# vesc_drv8301.net
KiCad netlist of a schematic drawn in Altium Designer
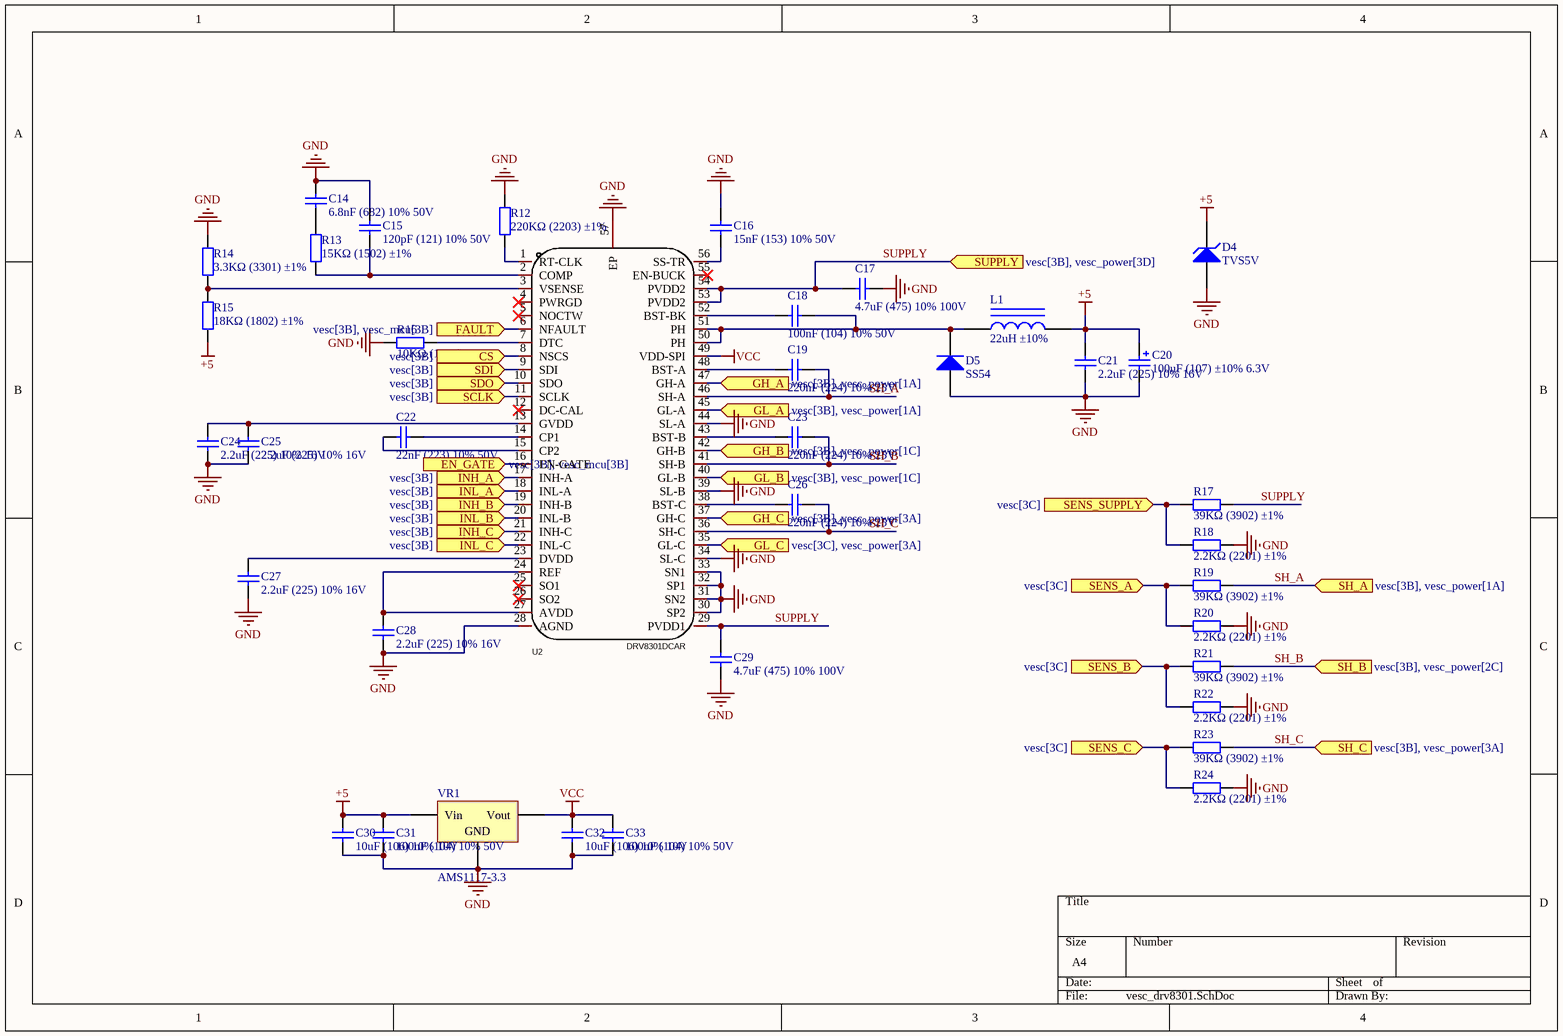
[diagram p0: vesc_drv8301.SchDoc]

(export (version "E")
  (design (tool "Eeschema 10.0.6"))
  (components
    (comp (ref "C14")
      (value "6.8nF (682) 10% 50V")
      (footprint "0603_C")
      (description "贴片电容")
      (libsource (lib "Miscellaneous Devices LC") (part "0603 6.8nF (682) 10% 50V"))
    )
    (comp (ref "C15")
      (value "120pF (121) 10% 50V")
      (footprint "0603_C")
      (description "贴片电容")
      (libsource (lib "Miscellaneous Devices LC") (part "0603 150pF (151) 10% 50V"))
    )
    (comp (ref "C16")
      (value "15nF (153) 10% 50V")
      (footprint "0603_C")
      (description "贴片电容")
      (libsource (lib "Miscellaneous Devices LC") (part "0603 15nF (153) 10% 50V"))
    )
    (comp (ref "C17")
      (value "4.7uF (475) 10% 100V")
      (footprint "1210_C")
      (description "贴片电容")
      (libsource (lib "Miscellaneous Devices LC") (part "1206 4.7uF (475) 10% 50V"))
    )
    (comp (ref "C18")
      (value "100nF (104) 10% 50V")
      (footprint "0603_C")
      (description "贴片电容")
      (libsource (lib "Miscellaneous Devices LC") (part "0603 100nF (104) 10% 50V"))
    )
    (comp (ref "C19")
      (value "220nF (224) 10% 25V")
      (footprint "0603_C")
      (description "贴片电容")
      (libsource (lib "Miscellaneous Devices LC") (part "0603 220nF (224) 10% 25V"))
    )
    (comp (ref "C20")
      (value "100uF (107) ±10% 6.3V")
      (footprint "CASE-B_3528")
      (description "钽电容")
      (libsource (lib "Miscellaneous Devices LC") (part "3528 100uF (107) 10% 6.3V"))
    )
    (comp (ref "C21")
      (value "2.2uF (225) 10% 16V")
      (footprint "0603_C")
      (description "贴片电容")
      (libsource (lib "Miscellaneous Devices LC") (part "0603 2.2uF (225) 10% 16V"))
    )
    (comp (ref "C22")
      (value "22nF (223) 10% 50V")
      (footprint "0603_C")
      (description "贴片电容")
      (libsource (lib "Miscellaneous Devices LC") (part "0603 22nF (223) 10% 50V"))
    )
    (comp (ref "C23")
      (value "220nF (224) 10% 25V")
      (footprint "0603_C")
      (description "贴片电容")
      (libsource (lib "Miscellaneous Devices LC") (part "0603 220nF (224) 10% 25V"))
    )
    (comp (ref "C24")
      (value "2.2uF (225) 10% 16V")
      (footprint "0603_C")
      (description "贴片电容")
      (libsource (lib "Miscellaneous Devices LC") (part "0603 2.2uF (225) 10% 16V"))
    )
    (comp (ref "C25")
      (value "2.2uF (225) 10% 16V")
      (footprint "0603_C")
      (description "贴片电容")
      (libsource (lib "Miscellaneous Devices LC") (part "0603 2.2uF (225) 10% 16V"))
    )
    (comp (ref "C26")
      (value "220nF (224) 10% 25V")
      (footprint "0603_C")
      (description "贴片电容")
      (libsource (lib "Miscellaneous Devices LC") (part "0603 220nF (224) 10% 25V"))
    )
    (comp (ref "C27")
      (value "2.2uF (225) 10% 16V")
      (footprint "0603_C")
      (description "贴片电容")
      (libsource (lib "Miscellaneous Devices LC") (part "0603 2.2uF (225) 10% 16V"))
    )
    (comp (ref "C28")
      (value "2.2uF (225) 10% 16V")
      (footprint "0603_C")
      (description "贴片电容")
      (libsource (lib "Miscellaneous Devices LC") (part "0603 2.2uF (225) 10% 16V"))
    )
    (comp (ref "C29")
      (value "4.7uF (475) 10% 100V")
      (footprint "1210_C")
      (description "贴片电容")
      (libsource (lib "Miscellaneous Devices LC") (part "1206 4.7uF (475) 10% 50V"))
    )
    (comp (ref "C30")
      (value "10uF (106) 10% 10V")
      (footprint "0603_C")
      (description "贴片电容")
      (libsource (lib "Miscellaneous Devices LC") (part "0603 10uF (106) 10% 10V"))
    )
    (comp (ref "C31")
      (value "100nF (104) 10% 50V")
      (footprint "0603_C")
      (description "贴片电容")
      (libsource (lib "Miscellaneous Devices LC") (part "0603 100nF (104) 10% 50V"))
    )
    (comp (ref "C32")
      (value "10uF (106) 10% 10V")
      (footprint "0603_C")
      (description "贴片电容")
      (libsource (lib "Miscellaneous Devices LC") (part "0603 10uF (106) 10% 10V"))
    )
    (comp (ref "C33")
      (value "100nF (104) 10% 50V")
      (footprint "0603_C")
      (description "贴片电容")
      (libsource (lib "Miscellaneous Devices LC") (part "0603 100nF (104) 10% 50V"))
    )
    (comp (ref "D4")
      (value "TVS5V")
      (footprint "SMA(DO-214AC)_S2")
      (description "稳压二极管")
      (libsource (lib "Miscellaneous Devices LC") (part "LL-34 ZMM5V6"))
    )
    (comp (ref "D5")
      (value "SS54")
      (footprint "SMA(DO-214AC)_S1")
      (description "二极管")
      (libsource (lib "Miscellaneous Devices LC") (part "SMA(DO-214AC) SS54"))
    )
    (comp (ref "L1")
      (value "22uH ±10%")
      (footprint "IND-SMD_L7.3-W6.6")
      (description "贴片电感")
      (libsource (lib "Miscellaneous Devices LC") (part "0805 22uH 10%"))
    )
    (comp (ref "R12")
      (value "220KΩ (2203) ±1%")
      (footprint "0603_R")
      (description "贴片电阻")
      (libsource (lib "Miscellaneous Devices LC") (part "0603 220KΩ (2203) 1%"))
    )
    (comp (ref "R13")
      (value "15KΩ (1502) ±1%")
      (footprint "0603_R")
      (description "贴片电阻")
      (libsource (lib "Miscellaneous Devices LC") (part "0603 15KΩ (1502) 1%"))
    )
    (comp (ref "R14")
      (value "3.3KΩ (3301) ±1%")
      (footprint "0603_R")
      (description "贴片电阻")
      (libsource (lib "Miscellaneous Devices LC") (part "0603 3.3KΩ (3301) 1%"))
    )
    (comp (ref "R15")
      (value "18KΩ (1802) ±1%")
      (footprint "0603_R")
      (description "贴片电阻")
      (libsource (lib "Miscellaneous Devices LC") (part "0603 18KΩ (1802) 1%"))
    )
    (comp (ref "R16")
      (value "10KΩ (1002) ±1%")
      (footprint "0603_R")
      (description "贴片电阻")
      (libsource (lib "Miscellaneous Devices LC") (part "0603 10KΩ (1002) 1%"))
    )
    (comp (ref "R17")
      (value "39KΩ (3902) ±1%")
      (footprint "0603_R")
      (description "贴片电阻")
      (libsource (lib "Miscellaneous Devices LC") (part "0603 39KΩ (3902) 1%"))
    )
    (comp (ref "R18")
      (value "2.2KΩ (2201) ±1%")
      (footprint "0603_R")
      (description "贴片电阻")
      (libsource (lib "Miscellaneous Devices LC") (part "0603 2.2KΩ (2201) 1%"))
    )
    (comp (ref "R19")
      (value "39KΩ (3902) ±1%")
      (footprint "0603_R")
      (description "贴片电阻")
      (libsource (lib "Miscellaneous Devices LC") (part "0603 39KΩ (3902) 1%"))
    )
    (comp (ref "R20")
      (value "2.2KΩ (2201) ±1%")
      (footprint "0603_R")
      (description "贴片电阻")
      (libsource (lib "Miscellaneous Devices LC") (part "0603 2.2KΩ (2201) 1%"))
    )
    (comp (ref "R21")
      (value "39KΩ (3902) ±1%")
      (footprint "0603_R")
      (description "贴片电阻")
      (libsource (lib "Miscellaneous Devices LC") (part "0603 39KΩ (3902) 1%"))
    )
    (comp (ref "R22")
      (value "2.2KΩ (2201) ±1%")
      (footprint "0603_R")
      (description "贴片电阻")
      (libsource (lib "Miscellaneous Devices LC") (part "0603 2.2KΩ (2201) 1%"))
    )
    (comp (ref "R23")
      (value "39KΩ (3902) ±1%")
      (footprint "0603_R")
      (description "贴片电阻")
      (libsource (lib "Miscellaneous Devices LC") (part "0603 39KΩ (3902) 1%"))
    )
    (comp (ref "R24")
      (value "2.2KΩ (2201) ±1%")
      (footprint "0603_R")
      (description "贴片电阻")
      (libsource (lib "Miscellaneous Devices LC") (part "0603 2.2KΩ (2201) 1%"))
    )
    (comp (ref "U2")
      (value "DRV8301DCAR")
      (footprint "HTSSOP-56_L14.0-W6.0-P0.50-LS8.0-BL")
      (fields (field (name "MANUFACTURER") "TI(德州仪器)"))
      (libsource (lib "vesc") (part "DRV8301DCAR"))
    )
    (comp (ref "VR1")
      (value "AMS1117-3.3")
      (footprint "SOT-223")
      (description "低压差线性稳压(LDO)")
      (libsource (lib "Miscellaneous Devices LC") (part "SOT-223 AMS1117-3.3"))
    )
  )
  (nets
    (net (code "1") (name "+5") (class "Default")
      (node (ref "C20") (pin "1") (pinfunction "1_1") (pintype "passive"))
      (node (ref "C21") (pin "2") (pinfunction "2_2") (pintype "passive"))
      (node (ref "C30") (pin "2") (pinfunction "2_2") (pintype "passive"))
      (node (ref "C31") (pin "2") (pinfunction "2_2") (pintype "passive"))
      (node (ref "D4") (pin "2") (pinfunction "K_2") (pintype "passive"))
      (node (ref "L1") (pin "2") (pinfunction "2_2") (pintype "passive"))
      (node (ref "R15") (pin "1") (pinfunction "1_1") (pintype "passive"))
      (node (ref "VR1") (pin "3") (pinfunction "Vin_3") (pintype "passive"))
    )
    (net (code "2") (name "/CS") (class "Default")
      (node (ref "U2") (pin "8") (pinfunction "NSCS_8") (pintype "passive"))
    )
    (net (code "3") (name "/EN_GATE") (class "Default")
      (node (ref "U2") (pin "16") (pinfunction "EN-GATE_16") (pintype "passive"))
    )
    (net (code "4") (name "/FAULT") (class "Default")
      (node (ref "U2") (pin "6") (pinfunction "NFAULT_6") (pintype "passive"))
    )
    (net (code "5") (name "/GH_A") (class "Default")
      (node (ref "U2") (pin "47") (pinfunction "GH-A_47") (pintype "passive"))
    )
    (net (code "6") (name "/GH_B") (class "Default")
      (node (ref "U2") (pin "42") (pinfunction "GH-B_42") (pintype "passive"))
    )
    (net (code "7") (name "/GH_C") (class "Default")
      (node (ref "U2") (pin "37") (pinfunction "GH-C_37") (pintype "passive"))
    )
    (net (code "8") (name "/GL_A") (class "Default")
      (node (ref "U2") (pin "45") (pinfunction "GL-A_45") (pintype "passive"))
    )
    (net (code "9") (name "/GL_B") (class "Default")
      (node (ref "U2") (pin "40") (pinfunction "GL-B_40") (pintype "passive"))
    )
    (net (code "10") (name "/GL_C") (class "Default")
      (node (ref "U2") (pin "35") (pinfunction "GL-C_35") (pintype "passive"))
    )
    (net (code "11") (name "/INH_A") (class "Default")
      (node (ref "U2") (pin "17") (pinfunction "INH-A_17") (pintype "passive"))
    )
    (net (code "12") (name "/INH_B") (class "Default")
      (node (ref "U2") (pin "19") (pinfunction "INH-B_19") (pintype "passive"))
    )
    (net (code "13") (name "/INH_C") (class "Default")
      (node (ref "U2") (pin "21") (pinfunction "INH-C_21") (pintype "passive"))
    )
    (net (code "14") (name "/INL_A") (class "Default")
      (node (ref "U2") (pin "18") (pinfunction "INL-A_18") (pintype "passive"))
    )
    (net (code "15") (name "/INL_B") (class "Default")
      (node (ref "U2") (pin "20") (pinfunction "INL-B_20") (pintype "passive"))
    )
    (net (code "16") (name "/INL_C") (class "Default")
      (node (ref "U2") (pin "22") (pinfunction "INL-C_22") (pintype "passive"))
    )
    (net (code "17") (name "/SCLK") (class "Default")
      (node (ref "U2") (pin "11") (pinfunction "SCLK_11") (pintype "passive"))
    )
    (net (code "18") (name "/SDI") (class "Default")
      (node (ref "U2") (pin "9") (pinfunction "SDI_9") (pintype "passive"))
    )
    (net (code "19") (name "/SDO") (class "Default")
      (node (ref "U2") (pin "10") (pinfunction "SDO_10") (pintype "passive"))
    )
    (net (code "20") (name "/SENS_A") (class "Default")
      (node (ref "R19") (pin "1") (pinfunction "1_1") (pintype "passive"))
      (node (ref "R20") (pin "1") (pinfunction "1_1") (pintype "passive"))
    )
    (net (code "21") (name "/SENS_B") (class "Default")
      (node (ref "R21") (pin "1") (pinfunction "1_1") (pintype "passive"))
      (node (ref "R22") (pin "1") (pinfunction "1_1") (pintype "passive"))
    )
    (net (code "22") (name "/SENS_C") (class "Default")
      (node (ref "R23") (pin "1") (pinfunction "1_1") (pintype "passive"))
      (node (ref "R24") (pin "1") (pinfunction "1_1") (pintype "passive"))
    )
    (net (code "23") (name "/SENS_SUPPLY") (class "Default")
      (node (ref "R17") (pin "1") (pinfunction "1_1") (pintype "passive"))
      (node (ref "R18") (pin "1") (pinfunction "1_1") (pintype "passive"))
    )
    (net (code "24") (name "/SH_A") (class "Default")
      (node (ref "C19") (pin "2") (pinfunction "2_2") (pintype "passive"))
      (node (ref "R19") (pin "2") (pinfunction "2_2") (pintype "passive"))
      (node (ref "U2") (pin "46") (pinfunction "SH-A_46") (pintype "passive"))
    )
    (net (code "25") (name "/SH_B") (class "Default")
      (node (ref "C23") (pin "2") (pinfunction "2_2") (pintype "passive"))
      (node (ref "R21") (pin "2") (pinfunction "2_2") (pintype "passive"))
      (node (ref "U2") (pin "41") (pinfunction "SH-B_41") (pintype "passive"))
    )
    (net (code "26") (name "/SH_C") (class "Default")
      (node (ref "C26") (pin "2") (pinfunction "2_2") (pintype "passive"))
      (node (ref "R23") (pin "2") (pinfunction "2_2") (pintype "passive"))
      (node (ref "U2") (pin "36") (pinfunction "SH-C_36") (pintype "passive"))
    )
    (net (code "27") (name "/SUPPLY") (class "Default")
      (node (ref "C17") (pin "1") (pinfunction "1_1") (pintype "passive"))
      (node (ref "C29") (pin "2") (pinfunction "2_2") (pintype "passive"))
      (node (ref "R17") (pin "2") (pinfunction "2_2") (pintype "passive"))
      (node (ref "U2") (pin "29") (pinfunction "PVDD1_29") (pintype "passive"))
      (node (ref "U2") (pin "53") (pinfunction "PVDD2_53") (pintype "passive"))
      (node (ref "U2") (pin "54") (pinfunction "PVDD2_54") (pintype "passive"))
    )
    (net (code "28") (name "GND") (class "Default")
      (node (ref "C14") (pin "2") (pinfunction "2_2") (pintype "passive"))
      (node (ref "C15") (pin "2") (pinfunction "2_2") (pintype "passive"))
      (node (ref "C16") (pin "2") (pinfunction "2_2") (pintype "passive"))
      (node (ref "C17") (pin "2") (pinfunction "2_2") (pintype "passive"))
      (node (ref "C20") (pin "2") (pinfunction "2_2") (pintype "passive"))
      (node (ref "C21") (pin "1") (pinfunction "1_1") (pintype "passive"))
      (node (ref "C24") (pin "1") (pinfunction "1_1") (pintype "passive"))
      (node (ref "C25") (pin "1") (pinfunction "1_1") (pintype "passive"))
      (node (ref "C27") (pin "1") (pinfunction "1_1") (pintype "passive"))
      (node (ref "C28") (pin "1") (pinfunction "1_1") (pintype "passive"))
      (node (ref "C29") (pin "1") (pinfunction "1_1") (pintype "passive"))
      (node (ref "C30") (pin "1") (pinfunction "1_1") (pintype "passive"))
      (node (ref "C31") (pin "1") (pinfunction "1_1") (pintype "passive"))
      (node (ref "C32") (pin "1") (pinfunction "1_1") (pintype "passive"))
      (node (ref "C33") (pin "1") (pinfunction "1_1") (pintype "passive"))
      (node (ref "D4") (pin "1") (pinfunction "A_1") (pintype "passive"))
      (node (ref "D5") (pin "1") (pinfunction "A_1") (pintype "passive"))
      (node (ref "R12") (pin "2") (pinfunction "2_2") (pintype "passive"))
      (node (ref "R14") (pin "2") (pinfunction "2_2") (pintype "passive"))
      (node (ref "R16") (pin "1") (pinfunction "1_1") (pintype "passive"))
      (node (ref "R18") (pin "2") (pinfunction "2_2") (pintype "passive"))
      (node (ref "R20") (pin "2") (pinfunction "2_2") (pintype "passive"))
      (node (ref "R22") (pin "2") (pinfunction "2_2") (pintype "passive"))
      (node (ref "R24") (pin "2") (pinfunction "2_2") (pintype "passive"))
      (node (ref "U2") (pin "28") (pinfunction "AGND_28") (pintype "passive"))
      (node (ref "U2") (pin "30") (pinfunction "SP2_30") (pintype "passive"))
      (node (ref "U2") (pin "31") (pinfunction "SN2_31") (pintype "passive"))
      (node (ref "U2") (pin "32") (pinfunction "SP1_32") (pintype "passive"))
      (node (ref "U2") (pin "33") (pinfunction "SN1_33") (pintype "passive"))
      (node (ref "U2") (pin "34") (pinfunction "SL-C_34") (pintype "passive"))
      (node (ref "U2") (pin "39") (pinfunction "SL-B_39") (pintype "passive"))
      (node (ref "U2") (pin "44") (pinfunction "SL-A_44") (pintype "passive"))
      (node (ref "U2") (pin "57") (pinfunction "EP_57") (pintype "passive"))
      (node (ref "VR1") (pin "1") (pinfunction "GND_1") (pintype "passive"))
    )
    (net (code "29") (name "Net-(C14-Pad1)") (class "Default")
      (node (ref "C14") (pin "1") (pinfunction "1_1") (pintype "passive"))
      (node (ref "R13") (pin "2") (pinfunction "2_2") (pintype "passive"))
    )
    (net (code "30") (name "Net-(D5-K)") (class "Default")
      (node (ref "C18") (pin "2") (pinfunction "2_2") (pintype "passive"))
      (node (ref "D5") (pin "2") (pinfunction "K_2") (pintype "passive"))
      (node (ref "L1") (pin "1") (pinfunction "1_1") (pintype "passive"))
      (node (ref "U2") (pin "50") (pinfunction "PH_50") (pintype "passive"))
      (node (ref "U2") (pin "51") (pinfunction "PH_51") (pintype "passive"))
    )
    (net (code "31") (name "Net-(U2-AVDD)") (class "Default")
      (node (ref "C28") (pin "2") (pinfunction "2_2") (pintype "passive"))
      (node (ref "U2") (pin "24") (pinfunction "REF_24") (pintype "passive"))
      (node (ref "U2") (pin "27") (pinfunction "AVDD_27") (pintype "passive"))
    )
    (net (code "32") (name "Net-(U2-BST-A)") (class "Default")
      (node (ref "C19") (pin "1") (pinfunction "1_1") (pintype "passive"))
      (node (ref "U2") (pin "48") (pinfunction "BST-A_48") (pintype "passive"))
    )
    (net (code "33") (name "Net-(U2-BST-B)") (class "Default")
      (node (ref "C23") (pin "1") (pinfunction "1_1") (pintype "passive"))
      (node (ref "U2") (pin "43") (pinfunction "BST-B_43") (pintype "passive"))
    )
    (net (code "34") (name "Net-(U2-BST-BK)") (class "Default")
      (node (ref "C18") (pin "1") (pinfunction "1_1") (pintype "passive"))
      (node (ref "U2") (pin "52") (pinfunction "BST-BK_52") (pintype "passive"))
    )
    (net (code "35") (name "Net-(U2-BST-C)") (class "Default")
      (node (ref "C26") (pin "1") (pinfunction "1_1") (pintype "passive"))
      (node (ref "U2") (pin "38") (pinfunction "BST-C_38") (pintype "passive"))
    )
    (net (code "36") (name "Net-(U2-COMP)") (class "Default")
      (node (ref "C15") (pin "1") (pinfunction "1_1") (pintype "passive"))
      (node (ref "R13") (pin "1") (pinfunction "1_1") (pintype "passive"))
      (node (ref "U2") (pin "2") (pinfunction "COMP_2") (pintype "passive"))
    )
    (net (code "37") (name "Net-(U2-CP1)") (class "Default")
      (node (ref "C22") (pin "2") (pinfunction "2_2") (pintype "passive"))
      (node (ref "U2") (pin "14") (pinfunction "CP1_14") (pintype "passive"))
    )
    (net (code "38") (name "Net-(U2-CP2)") (class "Default")
      (node (ref "C22") (pin "1") (pinfunction "1_1") (pintype "passive"))
      (node (ref "U2") (pin "15") (pinfunction "CP2_15") (pintype "passive"))
    )
    (net (code "39") (name "Net-(U2-DTC)") (class "Default")
      (node (ref "R16") (pin "2") (pinfunction "2_2") (pintype "passive"))
      (node (ref "U2") (pin "7") (pinfunction "DTC_7") (pintype "passive"))
    )
    (net (code "40") (name "Net-(U2-DVDD)") (class "Default")
      (node (ref "C27") (pin "2") (pinfunction "2_2") (pintype "passive"))
      (node (ref "U2") (pin "23") (pinfunction "DVDD_23") (pintype "passive"))
    )
    (net (code "41") (name "Net-(U2-GVDD)") (class "Default")
      (node (ref "C24") (pin "2") (pinfunction "2_2") (pintype "passive"))
      (node (ref "C25") (pin "2") (pinfunction "2_2") (pintype "passive"))
      (node (ref "U2") (pin "13") (pinfunction "GVDD_13") (pintype "passive"))
    )
    (net (code "42") (name "Net-(U2-RT-CLK)") (class "Default")
      (node (ref "R12") (pin "1") (pinfunction "1_1") (pintype "passive"))
      (node (ref "U2") (pin "1") (pinfunction "RT-CLK_1") (pintype "passive"))
    )
    (net (code "43") (name "Net-(U2-SS-TR)") (class "Default")
      (node (ref "C16") (pin "1") (pinfunction "1_1") (pintype "passive"))
      (node (ref "U2") (pin "56") (pinfunction "SS-TR_56") (pintype "passive"))
    )
    (net (code "44") (name "Net-(U2-VSENSE)") (class "Default")
      (node (ref "R14") (pin "1") (pinfunction "1_1") (pintype "passive"))
      (node (ref "R15") (pin "2") (pinfunction "2_2") (pintype "passive"))
      (node (ref "U2") (pin "3") (pinfunction "VSENSE_3") (pintype "passive"))
    )
    (net (code "45") (name "VCC") (class "Default")
      (node (ref "C32") (pin "2") (pinfunction "2_2") (pintype "passive"))
      (node (ref "C33") (pin "2") (pinfunction "2_2") (pintype "passive"))
      (node (ref "U2") (pin "49") (pinfunction "VDD-SPI_49") (pintype "passive"))
      (node (ref "VR1") (pin "2") (pinfunction "Vout_2") (pintype "passive"))
    )
    (net (code "46") (name "unconnected-(U2-DC-CAL-Pad12)") (class "Default")
      (node (ref "U2") (pin "12") (pinfunction "DC-CAL_12") (pintype "passive+no_connect"))
    )
    (net (code "47") (name "unconnected-(U2-EN-BUCK-Pad55)") (class "Default")
      (node (ref "U2") (pin "55") (pinfunction "EN-BUCK_55") (pintype "passive+no_connect"))
    )
    (net (code "48") (name "unconnected-(U2-NOCTW-Pad5)") (class "Default")
      (node (ref "U2") (pin "5") (pinfunction "NOCTW_5") (pintype "passive+no_connect"))
    )
    (net (code "49") (name "unconnected-(U2-PWRGD-Pad4)") (class "Default")
      (node (ref "U2") (pin "4") (pinfunction "PWRGD_4") (pintype "passive+no_connect"))
    )
    (net (code "50") (name "unconnected-(U2-SO1-Pad25)") (class "Default")
      (node (ref "U2") (pin "25") (pinfunction "SO1_25") (pintype "passive+no_connect"))
    )
    (net (code "51") (name "unconnected-(U2-SO2-Pad26)") (class "Default")
      (node (ref "U2") (pin "26") (pinfunction "SO2_26") (pintype "passive+no_connect"))
    )
  )
)
